# PWRMOD-001-RevA.net
KiCad netlist of a schematic drawn in Altium Designer
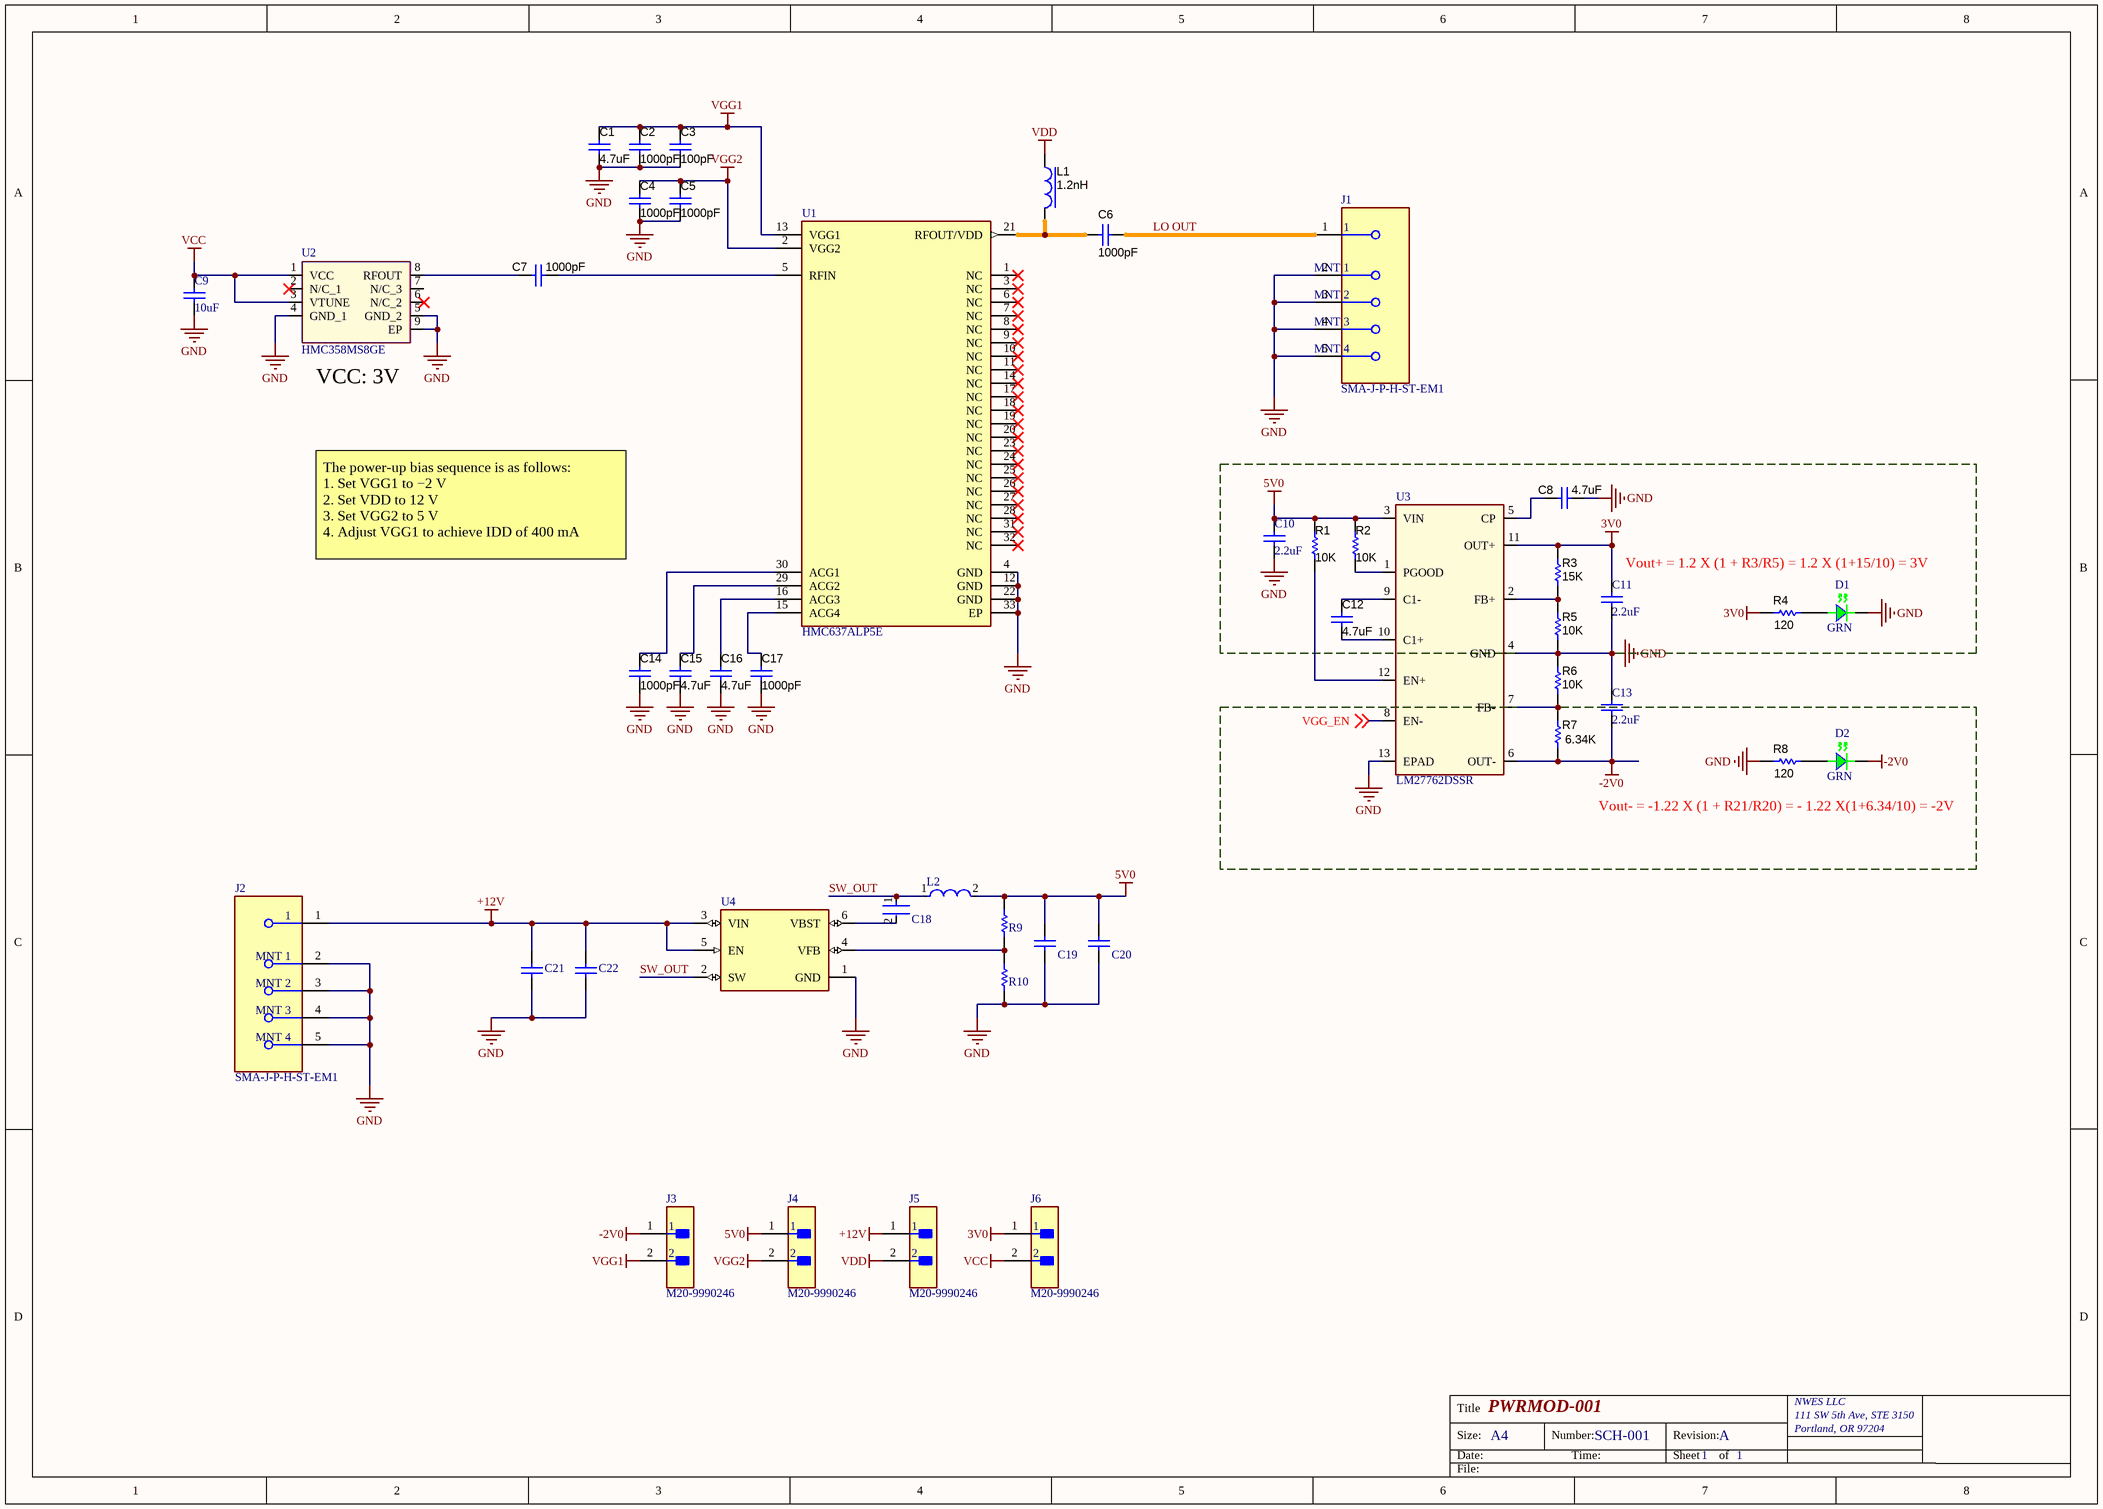
[diagram p0: PWRMOD-001-RevA.SchDoc]

(export (version "E")
  (design (tool "Eeschema 10.0.6"))
  (components
    (comp (ref "C1")
      (value "4.7uF")
      (footprint "0402_CAP")
      (description "CAP CER 4.7UF 10V X5R 0402")
      (fields
        (field (name "MANUFACTURER") "Samsung Electro-Mechanics")
        (field (name "PARTNUMBER") "CL05A475MP5NRNC")
      )
      (libsource (lib "Cold Junction") (part "CAP CER 4.7UF 10V X5R 0402"))
    )
    (comp (ref "C2")
      (value "1000pF")
      (footprint "0402_CAP")
      (description "CAP CER 1000PF 25V X7R 0402")
      (fields
        (field (name "MANUFACTURER") "KEMET")
        (field (name "MANUFACTURER PART NUMBER") "C0402C102J3RECAUTO")
      )
      (libsource (lib "Cold Junction") (part "Capacitor"))
    )
    (comp (ref "C3")
      (value "100pF")
      (footprint "0402_CAP")
      (description "CAP CER 100PF 25V X7R 0402")
      (fields (field (name "MANUFACTURER") "AVX Corporation") (field (name "PARTNUMBER") "04023C101KAT2A"))
      (libsource (lib "Cold Junction") (part "Capacitor"))
    )
    (comp (ref "C4")
      (value "1000pF")
      (footprint "0402_CAP")
      (description "CAP CER 1000PF 25V X7R 0402")
      (fields
        (field (name "MANUFACTURER") "KEMET")
        (field (name "MANUFACTURER PART NUMBER") "C0402C102J3RECAUTO")
      )
      (libsource (lib "Cold Junction") (part "Capacitor"))
    )
    (comp (ref "C5")
      (value "1000pF")
      (footprint "0402_CAP")
      (description "CAP CER 1000PF 25V X7R 0402")
      (fields
        (field (name "MANUFACTURER") "KEMET")
        (field (name "MANUFACTURER PART NUMBER") "C0402C102J3RECAUTO")
      )
      (libsource (lib "Cold Junction") (part "Capacitor"))
    )
    (comp (ref "C6")
      (value "1000pF")
      (footprint "0402_CAP")
      (description "CAP CER 1000PF 25V X7R 0402")
      (fields
        (field (name "MANUFACTURER") "KEMET")
        (field (name "MANUFACTURER PART NUMBER") "C0402C102J3RECAUTO")
      )
      (libsource (lib "Cold Junction") (part "Capacitor"))
    )
    (comp (ref "C7")
      (value "1000pF")
      (footprint "0402_CAP")
      (description "CAP CER 1000PF 50V C0G/NP0 0402")
      (fields
        (field (name "MANUFACTURER") "Murata Electronics")
        (field (name "PARTNUMBER") "GCM1555C1H102FA16D")
      )
      (libsource (lib "Cold Junction") (part "Capacitor"))
    )
    (comp (ref "C8")
      (value "4.7uF")
      (footprint "0402_CAP")
      (description "CAP CER 4.7UF 10V X5R 0402")
      (fields
        (field (name "MANUFACTURER") "Samsung Electro-Mechanics")
        (field (name "PARTNUMBER") "CL05A475MP5NRNC")
      )
      (libsource (lib "Cold Junction") (part "CAP CER 4.7UF 10V X5R 0402"))
    )
    (comp (ref "C9")
      (value "10uF")
      (footprint "0402_CAP")
      (description "CAP CER 10UF 6.3V X5R 0402")
      (fields
        (field (name "MANUFACTURER") "Murata Electronics")
        (field (name "PARTNUMBER") "GRJ155R60J106ME11D")
      )
      (libsource (lib "Cold Junction") (part "Cap"))
    )
    (comp (ref "C10")
      (value "2.2uF")
      (footprint "0402_CAP")
      (description "CAP CER 2.2UF 16V X6S 0402")
      (fields
        (field (name "MANUFACTURER") "TDK Corporation")
        (field (name "PARTNUMBER") "C1005X6S1C225M050BC")
      )
      (libsource (lib "Cold Junction") (part "Cap"))
    )
    (comp (ref "C11")
      (value "2.2uF")
      (footprint "0402_CAP")
      (description "CAP CER 2.2UF 16V X6S 0402")
      (fields
        (field (name "MANUFACTURER") "TDK Corporation")
        (field (name "PARTNUMBER") "C1005X6S1C225M050BC")
      )
      (libsource (lib "Cold Junction") (part "Cap"))
    )
    (comp (ref "C12")
      (value "4.7uF")
      (footprint "0402_CAP")
      (description "CAP CER 4.7UF 10V X5R 0402")
      (fields
        (field (name "MANUFACTURER") "Samsung Electro-Mechanics")
        (field (name "PARTNUMBER") "CL05A475MP5NRNC")
      )
      (libsource (lib "Cold Junction") (part "CAP CER 4.7UF 10V X5R 0402"))
    )
    (comp (ref "C13")
      (value "2.2uF")
      (footprint "0402_CAP")
      (description "CAP CER 2.2UF 16V X6S 0402")
      (fields
        (field (name "MANUFACTURER") "TDK Corporation")
        (field (name "PARTNUMBER") "C1005X6S1C225M050BC")
      )
      (libsource (lib "Cold Junction") (part "Cap"))
    )
    (comp (ref "C14")
      (value "1000pF")
      (footprint "0402_CAP")
      (description "CAP CER 1000PF 25V X7R 0402")
      (fields
        (field (name "MANUFACTURER") "KEMET")
        (field (name "MANUFACTURER PART NUMBER") "C0402C102J3RECAUTO")
      )
      (libsource (lib "Cold Junction") (part "Capacitor"))
    )
    (comp (ref "C15")
      (value "4.7uF")
      (footprint "0402_CAP")
      (description "CAP CER 4.7UF 10V X5R 0402")
      (fields
        (field (name "MANUFACTURER") "Samsung Electro-Mechanics")
        (field (name "PARTNUMBER") "CL05A475MP5NRNC")
      )
      (libsource (lib "Cold Junction") (part "CAP CER 4.7UF 10V X5R 0402"))
    )
    (comp (ref "C16")
      (value "4.7uF")
      (footprint "0402_CAP")
      (description "CAP CER 4.7UF 10V X5R 0402")
      (fields
        (field (name "MANUFACTURER") "Samsung Electro-Mechanics")
        (field (name "PARTNUMBER") "CL05A475MP5NRNC")
      )
      (libsource (lib "Cold Junction") (part "CAP CER 4.7UF 10V X5R 0402"))
    )
    (comp (ref "C17")
      (value "1000pF")
      (footprint "0402_CAP")
      (description "CAP CER 1000PF 25V X7R 0402")
      (fields
        (field (name "MANUFACTURER") "KEMET")
        (field (name "MANUFACTURER PART NUMBER") "C0402C102J3RECAUTO")
      )
      (libsource (lib "Cold Junction") (part "Capacitor"))
    )
    (comp (ref "C18")
      (value "C0603C104Z3VACTU")
      (footprint "FP-C0603-CG-IPC_B")
      (description "CAP CER 0.1UF 25V Y5V 0603")
      (fields (field (name "TOLERANCE") "80%") (field (name "VOLTAGE") "25V"))
      (libsource (lib "Altium Content Vault") (part "02cd4be3c70576c341d710602a673aa"))
    )
    (comp (ref "C19")
      (value "C1608X5R1A226M080AC")
      (footprint "CAPC1608X100X20ML10")
      (description "Chip Capacitor, 22 uF, +/- 20%, 10 V, -55 to 85 degC, 0603 (1608 Metric), RoHS, Tape and Reel")
      (fields (field (name "MANUFACTURER") "TDK") (field (name "TOLERANCE") "±20%"))
      (libsource (lib "Altium Content Vault") (part "CAP-NP-2"))
    )
    (comp (ref "C20")
      (value "C1608X5R1A226M080AC")
      (footprint "CAPC1608X100X20ML10")
      (description "Chip Capacitor, 22 uF, +/- 20%, 10 V, -55 to 85 degC, 0603 (1608 Metric), RoHS, Tape and Reel")
      (fields (field (name "MANUFACTURER") "TDK") (field (name "TOLERANCE") "±20%"))
      (libsource (lib "Altium Content Vault") (part "CAP-NP-2"))
    )
    (comp (ref "C21")
      (value "GRM31CR61E106KA12L")
      (footprint "CAPC3216X180X55ML20T25")
      (description "Chip Capacitor, 10 uF, +/- 10%, 25 V, -55 to 85 degC, 1206 (3216 Metric), RoHS, Tape and Reel")
      (fields (field (name "MANUFACTURER") "Murata") (field (name "TOLERANCE") "10%"))
      (libsource (lib "Altium Content Vault") (part "CAP-NP-2"))
    )
    (comp (ref "C22")
      (value "GRM31CR61E106KA12L")
      (footprint "CAPC3216X180X55ML20T25")
      (description "Chip Capacitor, 10 uF, +/- 10%, 25 V, -55 to 85 degC, 1206 (3216 Metric), RoHS, Tape and Reel")
      (fields (field (name "MANUFACTURER") "Murata") (field (name "TOLERANCE") "10%"))
      (libsource (lib "Altium Content Vault") (part "CAP-NP-2"))
    )
    (comp (ref "D1")
      (value "GRN")
      (footprint "LED_0603")
      (description "LED GREEN CLEAR CHIP 0603 SMD")
      (fields (field (name "MANUFACTURER") "Kingbright") (field (name "PARTNUMBER") "APTD1608CGCK"))
      (libsource (lib "Cold Junction") (part "0603LED_GRN"))
    )
    (comp (ref "D2")
      (value "GRN")
      (footprint "LED_0603")
      (description "LED GREEN CLEAR CHIP 0603 SMD")
      (fields (field (name "MANUFACTURER") "Kingbright") (field (name "PARTNUMBER") "APTD1608CGCK"))
      (libsource (lib "Cold Junction") (part "0603LED_GRN"))
    )
    (comp (ref "J1")
      (value "SMA-J-P-H-ST-EM1")
      (footprint "FP-SMA-J-P-H-ST-EM1-MFG")
      (description "CONN SMA JACK STR 50OHM EDGE MNT")
      (libsource (lib "") (part "c65b8a639cdaef1819ea20b5466f8fa_1"))
    )
    (comp (ref "J2")
      (value "SMA-J-P-H-ST-EM1")
      (footprint "FP-SMA-J-P-H-ST-EM1-MFG")
      (description "CONN SMA JACK STR 50OHM EDGE MNT")
      (libsource (lib "Altium Content Vault") (part "c65b8a639cdaef1819ea20b5466f8fa"))
    )
    (comp (ref "J3")
      (value "M20-9990246")
      (footprint "FP-M20-9990246-MFG")
      (description "CONN HEADER VERT 2POS 2.54MM")
      (fields
        (field (name "OCTOPART") "https://octopart.com/m20-9990246-harwin-2590635")
        (field (name "MANUFACTURER") "Harwin")
      )
      (libsource (lib "Altium Content Vault") (part "3bc925449376181038e59eaffc5286c"))
    )
    (comp (ref "J4")
      (value "M20-9990246")
      (footprint "FP-M20-9990246-MFG")
      (description "CONN HEADER VERT 2POS 2.54MM")
      (fields
        (field (name "OCTOPART") "https://octopart.com/m20-9990246-harwin-2590635")
        (field (name "MANUFACTURER") "Harwin")
      )
      (libsource (lib "Altium Content Vault") (part "3bc925449376181038e59eaffc5286c"))
    )
    (comp (ref "J5")
      (value "M20-9990246")
      (footprint "FP-M20-9990246-MFG")
      (description "CONN HEADER VERT 2POS 2.54MM")
      (fields
        (field (name "OCTOPART") "https://octopart.com/m20-9990246-harwin-2590635")
        (field (name "MANUFACTURER") "Harwin")
      )
      (libsource (lib "Altium Content Vault") (part "3bc925449376181038e59eaffc5286c"))
    )
    (comp (ref "J6")
      (value "M20-9990246")
      (footprint "FP-M20-9990246-MFG")
      (description "CONN HEADER VERT 2POS 2.54MM")
      (fields
        (field (name "OCTOPART") "https://octopart.com/m20-9990246-harwin-2590635")
        (field (name "MANUFACTURER") "Harwin")
      )
      (libsource (lib "Altium Content Vault") (part "3bc925449376181038e59eaffc5286c"))
    )
    (comp (ref "L1")
      (value "1.2nH")
      (footprint "IND_0201")
      (description "FIXED IND 1.2NH 1.1A 40MOHM SMD")
      (fields (field (name "PARTNUMBER") "LQP03HQ1N2B02D") (field (name "MANUFACTURER") "Murata Electronics"))
      (libsource (lib "Cold Junction") (part "INDUCTOR"))
    )
    (comp (ref "L2")
      (value "NRS8030T3R3MJGJ")
      (footprint "FP-NRS8030-MFG")
      (description "Inductor Power Shielded Wirewound 3.3uH 20% 100KHz Ferrite 4.2A 24.7mΩ DCR T/R")
      (fields (field (name "TOLERANCE") "20%"))
      (libsource (lib "Altium Content Vault") (part "725321dda6339637d4d059423bc1c3c"))
    )
    (comp (ref "R1")
      (value "10K")
      (footprint "0402_RES")
      (description "RES 10K OHM 1% 1/16W 0402")
      (fields
        (field (name "PARTNUMBER") "RMCF0402FT10K0")
        (field (name "VALUEDISPLAYED") "10K")
        (field (name "MANUFACTURER") "Stackpole Electronics Inc")
      )
      (libsource (lib "Cold Junction") (part "CMP-0026823-3"))
    )
    (comp (ref "R2")
      (value "10K")
      (footprint "0402_RES")
      (description "RES 10K OHM 1% 1/16W 0402")
      (fields
        (field (name "PARTNUMBER") "RMCF0402FT10K0")
        (field (name "VALUEDISPLAYED") "10K")
        (field (name "MANUFACTURER") "Stackpole Electronics Inc")
      )
      (libsource (lib "Cold Junction") (part "CMP-0026823-3"))
    )
    (comp (ref "R3")
      (value "15K")
      (footprint "0402_RES")
      (description "RES SMD 15K OHM 1% 1/16W 0402")
      (fields
        (field (name "PARTNUMBER") "RC0402FR-0715KL")
        (field (name "VALUEDISPLAYED") "15K")
        (field (name "MANUFACTURER") "Yageo")
      )
      (libsource (lib "Cold Junction") (part "CMP-0026823-3"))
    )
    (comp (ref "R4")
      (value "120")
      (footprint "0402_RES")
      (description "RES 120 OHM 1% 1/16W 0402")
      (fields (field (name "PARTNUMBER") "RC0402FR-07120RL") (field (name "MANUFACTURER") "Yageo"))
      (libsource (lib "Cold Junction") (part "RES 120 OHM 1% 1/16W 0402"))
    )
    (comp (ref "R5")
      (value "10K")
      (footprint "0402_RES")
      (description "RES 10K OHM 1% 1/16W 0402")
      (fields
        (field (name "PARTNUMBER") "RMCF0402FT10K0")
        (field (name "VALUEDISPLAYED") "10K")
        (field (name "MANUFACTURER") "Stackpole Electronics Inc")
      )
      (libsource (lib "Cold Junction") (part "CMP-0026823-3"))
    )
    (comp (ref "R6")
      (value "10K")
      (footprint "0402_RES")
      (description "RES 10K OHM 1% 1/16W 0402")
      (fields
        (field (name "PARTNUMBER") "RMCF0402FT10K0")
        (field (name "VALUEDISPLAYED") "10K")
        (field (name "MANUFACTURER") "Stackpole Electronics Inc")
      )
      (libsource (lib "Cold Junction") (part "CMP-0026823-3"))
    )
    (comp (ref "R7")
      (value "6.34K")
      (footprint "0402_RES")
      (description "RES 6.34K OHM 1% 1/16W 0402")
      (fields (field (name "PARTNUMBER") "RC0402FR-076K34L") (field (name "MANUFACTURER") "Yageo"))
      (libsource (lib "Cold Junction") (part "RES 6.34K OHM 1% 1/16W 0402"))
    )
    (comp (ref "R8")
      (value "120")
      (footprint "0402_RES")
      (description "RES 120 OHM 1% 1/16W 0402")
      (fields (field (name "PARTNUMBER") "RC0402FR-07120RL") (field (name "MANUFACTURER") "Yageo"))
      (libsource (lib "Cold Junction") (part "RES 120 OHM 1% 1/16W 0402"))
    )
    (comp (ref "R9")
      (value "CRCW020156K2FNED")
      (footprint "RESC0603X28X15NL05T05")
      (fields (field (name "MANUFACTURER") "Vishay Dale"))
      (libsource (lib "Altium Content Vault") (part "RES"))
    )
    (comp (ref "R10")
      (value "ERJ2RKF1002X")
      (footprint "RESC1005X40X25LL05T05")
      (description "Chip Resistor, 10 KOhm, +/- 1%, 0.1 W, -55 to 155 degC, 0402 (1005 Metric), RoHS, Tape and Reel")
      (fields (field (name "TOLERANCE") "1%") (field (name "MANUFACTURER") "Panasonic"))
      (libsource (lib "Altium Content Vault") (part "RES-2"))
    )
    (comp (ref "U1")
      (value "HMC637ALP5E")
      (footprint "FP-HCP-32-1-IPC_A")
      (description "IC MMIC MESFET GAAS 1W 32-QFN")
      (libsource (lib "Altium Content Vault") (part "0f5b40441086f0f622d6d4123b0df76"))
    )
    (comp (ref "U2")
      (value "HMC358MS8GE")
      (footprint "SOP65P488X110-9N")
      (description "IC MMIC AMP VCO BUFFER 8-MSOP")
      (fields (field (name "MANUFACTURER") "Analog Devices"))
      (libsource (lib "Cold Junction") (part "HMC358MS8GE"))
    )
    (comp (ref "U3")
      (value "LM27762DSSR")
      (footprint "SON50P200X300X80-13N-D")
      (description "LM27762 LOW-NOISE POSITIVE- AND")
      (fields
        (field (name "MANUFACTURER") "Texas Instruments")
        (field (name "MOUSER PART NUMBER") "595-LM27762DSSR")
      )
      (libsource (lib "Cold Junction") (part "LM27762DSSR"))
    )
    (comp (ref "U4")
      (value "TPS562201DDCR")
      (footprint "FP-DDC0006A-IPC_C")
      (description "IC REG BUCK ADJ 2A TSOT23-6")
      (fields (field (name "MANUFACTURER") "Texas Instruments"))
      (libsource (lib "Altium Content Vault") (part "957e164956730ea4bf6293280af19fc"))
    )
  )
  (nets
    (net (code "1") (name "+12V") (class "Default")
      (node (ref "C21") (pin "2") (pinfunction "2_2") (pintype "passive"))
      (node (ref "C22") (pin "2") (pinfunction "2_2") (pintype "passive"))
      (node (ref "J2") (pin "1") (pinfunction "1_1") (pintype "passive"))
      (node (ref "J5") (pin "1") (pinfunction "1_1") (pintype "passive"))
      (node (ref "U4") (pin "3") (pinfunction "VIN_3") (pintype "bidirectional"))
      (node (ref "U4") (pin "5") (pinfunction "EN_5") (pintype "input"))
    )
    (net (code "2") (name "-2V0") (class "Default")
      (node (ref "C13") (pin "1") (pinfunction "1_1") (pintype "passive"))
      (node (ref "D2") (pin "2") (pinfunction "K_2") (pintype "passive"))
      (node (ref "J3") (pin "1") (pinfunction "1_1") (pintype "passive"))
      (node (ref "R7") (pin "2") (pinfunction "2_2") (pintype "passive"))
      (node (ref "U3") (pin "6") (pinfunction "OUT-_6") (pintype "power_in"))
    )
    (net (code "3") (name "/LO OUT") (class "Default")
      (node (ref "C6") (pin "1") (pinfunction "1_1") (pintype "passive"))
      (node (ref "J1") (pin "1") (pinfunction "1_1") (pintype "passive"))
    )
    (net (code "4") (name "/SW_OUT") (class "Default")
      (node (ref "C18") (pin "1") (pinfunction "1_1") (pintype "passive"))
      (node (ref "L2") (pin "1") (pinfunction "1_1") (pintype "passive"))
      (node (ref "U4") (pin "2") (pinfunction "SW_2") (pintype "bidirectional"))
    )
    (net (code "5") (name "3V0") (class "Default")
      (node (ref "C11") (pin "2") (pinfunction "2_2") (pintype "passive"))
      (node (ref "J6") (pin "1") (pinfunction "1_1") (pintype "passive"))
      (node (ref "R3") (pin "1") (pinfunction "1_1") (pintype "passive"))
      (node (ref "R4") (pin "1") (pinfunction "1_1") (pintype "passive"))
      (node (ref "U3") (pin "11") (pinfunction "OUT+_11") (pintype "power_in"))
    )
    (net (code "6") (name "5V0") (class "Default")
      (node (ref "C10") (pin "2") (pinfunction "2_2") (pintype "passive"))
      (node (ref "C19") (pin "2") (pinfunction "2_2") (pintype "passive"))
      (node (ref "C20") (pin "2") (pinfunction "2_2") (pintype "passive"))
      (node (ref "J4") (pin "1") (pinfunction "1_1") (pintype "passive"))
      (node (ref "L2") (pin "2") (pinfunction "2_2") (pintype "passive"))
      (node (ref "R1") (pin "1") (pinfunction "1_1") (pintype "passive"))
      (node (ref "R2") (pin "1") (pinfunction "1_1") (pintype "passive"))
      (node (ref "R9") (pin "2") (pinfunction "2_2") (pintype "passive"))
      (node (ref "U3") (pin "3") (pinfunction "VIN_3") (pintype "power_in"))
    )
    (net (code "7") (name "GND") (class "Default")
      (node (ref "C1") (pin "1") (pinfunction "1_1") (pintype "passive"))
      (node (ref "C10") (pin "1") (pinfunction "1_1") (pintype "passive"))
      (node (ref "C11") (pin "1") (pinfunction "1_1") (pintype "passive"))
      (node (ref "C13") (pin "2") (pinfunction "2_2") (pintype "passive"))
      (node (ref "C14") (pin "1") (pinfunction "1_1") (pintype "passive"))
      (node (ref "C15") (pin "1") (pinfunction "1_1") (pintype "passive"))
      (node (ref "C16") (pin "1") (pinfunction "1_1") (pintype "passive"))
      (node (ref "C17") (pin "1") (pinfunction "1_1") (pintype "passive"))
      (node (ref "C19") (pin "1") (pinfunction "1_1") (pintype "passive"))
      (node (ref "C2") (pin "1") (pinfunction "1_1") (pintype "passive"))
      (node (ref "C20") (pin "1") (pinfunction "1_1") (pintype "passive"))
      (node (ref "C21") (pin "1") (pinfunction "1_1") (pintype "passive"))
      (node (ref "C22") (pin "1") (pinfunction "1_1") (pintype "passive"))
      (node (ref "C3") (pin "1") (pinfunction "1_1") (pintype "passive"))
      (node (ref "C4") (pin "1") (pinfunction "1_1") (pintype "passive"))
      (node (ref "C5") (pin "1") (pinfunction "1_1") (pintype "passive"))
      (node (ref "C8") (pin "2") (pinfunction "2_2") (pintype "passive"))
      (node (ref "C9") (pin "1") (pinfunction "1_1") (pintype "passive"))
      (node (ref "D1") (pin "2") (pinfunction "K_2") (pintype "passive"))
      (node (ref "J1") (pin "2") (pinfunction "MNT_1_2") (pintype "passive"))
      (node (ref "J1") (pin "3") (pinfunction "MNT_2_3") (pintype "passive"))
      (node (ref "J1") (pin "4") (pinfunction "MNT_3_4") (pintype "passive"))
      (node (ref "J1") (pin "5") (pinfunction "MNT_4_5") (pintype "passive"))
      (node (ref "J2") (pin "2") (pinfunction "MNT_1_2") (pintype "passive"))
      (node (ref "J2") (pin "3") (pinfunction "MNT_2_3") (pintype "passive"))
      (node (ref "J2") (pin "4") (pinfunction "MNT_3_4") (pintype "passive"))
      (node (ref "J2") (pin "5") (pinfunction "MNT_4_5") (pintype "passive"))
      (node (ref "R10") (pin "1") (pinfunction "1_1") (pintype "passive"))
      (node (ref "R5") (pin "2") (pinfunction "2_2") (pintype "passive"))
      (node (ref "R6") (pin "1") (pinfunction "1_1") (pintype "passive"))
      (node (ref "R8") (pin "1") (pinfunction "1_1") (pintype "passive"))
      (node (ref "U1") (pin "12") (pinfunction "GND_12") (pintype "power_in"))
      (node (ref "U1") (pin "22") (pinfunction "GND_22") (pintype "power_in"))
      (node (ref "U1") (pin "33") (pinfunction "EP_33") (pintype "power_in"))
      (node (ref "U1") (pin "4") (pinfunction "GND_4") (pintype "power_in"))
      (node (ref "U2") (pin "4") (pinfunction "GND_1_4") (pintype "passive"))
      (node (ref "U2") (pin "5") (pinfunction "GND_2_5") (pintype "passive"))
      (node (ref "U2") (pin "9") (pinfunction "EP_9") (pintype "passive"))
      (node (ref "U3") (pin "13") (pinfunction "EPAD_13") (pintype "passive"))
      (node (ref "U3") (pin "4") (pinfunction "GND_4") (pintype "passive"))
      (node (ref "U4") (pin "1") (pinfunction "GND_1") (pintype "power_in"))
    )
    (net (code "8") (name "Net-(D1-A)") (class "Default")
      (node (ref "D1") (pin "1") (pinfunction "A_1") (pintype "passive"))
      (node (ref "R4") (pin "2") (pinfunction "2_2") (pintype "passive"))
    )
    (net (code "9") (name "Net-(D2-A)") (class "Default")
      (node (ref "D2") (pin "1") (pinfunction "A_1") (pintype "passive"))
      (node (ref "R8") (pin "2") (pinfunction "2_2") (pintype "passive"))
    )
    (net (code "10") (name "Net-(U1-ACG1)") (class "Default")
      (node (ref "C14") (pin "2") (pinfunction "2_2") (pintype "passive"))
      (node (ref "U1") (pin "30") (pinfunction "ACG1_30") (pintype "power_in"))
    )
    (net (code "11") (name "Net-(U1-ACG2)") (class "Default")
      (node (ref "C15") (pin "2") (pinfunction "2_2") (pintype "passive"))
      (node (ref "U1") (pin "29") (pinfunction "ACG2_29") (pintype "power_in"))
    )
    (net (code "12") (name "Net-(U1-ACG3)") (class "Default")
      (node (ref "C16") (pin "2") (pinfunction "2_2") (pintype "passive"))
      (node (ref "U1") (pin "16") (pinfunction "ACG3_16") (pintype "power_in"))
    )
    (net (code "13") (name "Net-(U1-ACG4)") (class "Default")
      (node (ref "C17") (pin "2") (pinfunction "2_2") (pintype "passive"))
      (node (ref "U1") (pin "15") (pinfunction "ACG4_15") (pintype "power_in"))
    )
    (net (code "14") (name "Net-(U1-RFIN)") (class "Default")
      (node (ref "C7") (pin "2") (pinfunction "2_2") (pintype "passive"))
      (node (ref "U1") (pin "5") (pinfunction "RFIN_5") (pintype "passive"))
    )
    (net (code "15") (name "Net-(U1-RFOUT{slash}VDD)") (class "Default")
      (node (ref "C6") (pin "2") (pinfunction "2_2") (pintype "passive"))
      (node (ref "L1") (pin "2") (pinfunction "2_2") (pintype "passive"))
      (node (ref "U1") (pin "21") (pinfunction "RFOUT/VDD_21") (pintype "output"))
    )
    (net (code "16") (name "Net-(U2-RFOUT)") (class "Default")
      (node (ref "C7") (pin "1") (pinfunction "1_1") (pintype "passive"))
      (node (ref "U2") (pin "8") (pinfunction "RFOUT_8") (pintype "passive"))
    )
    (net (code "17") (name "Net-(U3-C1+)") (class "Default")
      (node (ref "C12") (pin "2") (pinfunction "2_2") (pintype "passive"))
      (node (ref "U3") (pin "10") (pinfunction "C1+_10") (pintype "power_in"))
    )
    (net (code "18") (name "Net-(U3-C1-)") (class "Default")
      (node (ref "C12") (pin "1") (pinfunction "1_1") (pintype "passive"))
      (node (ref "U3") (pin "9") (pinfunction "C1-_9") (pintype "power_in"))
    )
    (net (code "19") (name "Net-(U3-CP)") (class "Default")
      (node (ref "C8") (pin "1") (pinfunction "1_1") (pintype "passive"))
      (node (ref "U3") (pin "5") (pinfunction "CP_5") (pintype "power_in"))
    )
    (net (code "20") (name "Net-(U3-EN+)") (class "Default")
      (node (ref "R1") (pin "2") (pinfunction "2_2") (pintype "passive"))
      (node (ref "U3") (pin "12") (pinfunction "EN+_12") (pintype "passive"))
    )
    (net (code "21") (name "Net-(U3-FB+)") (class "Default")
      (node (ref "R3") (pin "2") (pinfunction "2_2") (pintype "passive"))
      (node (ref "R5") (pin "1") (pinfunction "1_1") (pintype "passive"))
      (node (ref "U3") (pin "2") (pinfunction "FB+_2") (pintype "power_in"))
    )
    (net (code "22") (name "Net-(U3-FB-)") (class "Default")
      (node (ref "R6") (pin "2") (pinfunction "2_2") (pintype "passive"))
      (node (ref "R7") (pin "1") (pinfunction "1_1") (pintype "passive"))
      (node (ref "U3") (pin "7") (pinfunction "FB-_7") (pintype "power_in"))
    )
    (net (code "23") (name "Net-(U3-PGOOD)") (class "Default")
      (node (ref "R2") (pin "2") (pinfunction "2_2") (pintype "passive"))
      (node (ref "U3") (pin "1") (pinfunction "PGOOD_1") (pintype "passive"))
    )
    (net (code "24") (name "Net-(U4-VBST)") (class "Default")
      (node (ref "C18") (pin "2") (pinfunction "2_2") (pintype "passive"))
      (node (ref "U4") (pin "6") (pinfunction "VBST_6") (pintype "bidirectional"))
    )
    (net (code "25") (name "Net-(U4-VFB)") (class "Default")
      (node (ref "R10") (pin "2") (pinfunction "2_2") (pintype "passive"))
      (node (ref "R9") (pin "1") (pinfunction "1_1") (pintype "passive"))
      (node (ref "U4") (pin "4") (pinfunction "VFB_4") (pintype "bidirectional"))
    )
    (net (code "26") (name "VCC") (class "Default")
      (node (ref "C9") (pin "2") (pinfunction "2_2") (pintype "passive"))
      (node (ref "J6") (pin "2") (pinfunction "2_2") (pintype "passive"))
      (node (ref "U2") (pin "1") (pinfunction "VCC_1") (pintype "passive"))
      (node (ref "U2") (pin "3") (pinfunction "VTUNE_3") (pintype "passive"))
    )
    (net (code "27") (name "VDD") (class "Default")
      (node (ref "J5") (pin "2") (pinfunction "2_2") (pintype "passive"))
      (node (ref "L1") (pin "1") (pinfunction "1_1") (pintype "passive"))
    )
    (net (code "28") (name "VGG1") (class "Default")
      (node (ref "C1") (pin "2") (pinfunction "2_2") (pintype "passive"))
      (node (ref "C2") (pin "2") (pinfunction "2_2") (pintype "passive"))
      (node (ref "C3") (pin "2") (pinfunction "2_2") (pintype "passive"))
      (node (ref "J3") (pin "2") (pinfunction "2_2") (pintype "passive"))
      (node (ref "U1") (pin "13") (pinfunction "VGG1_13") (pintype "power_in"))
    )
    (net (code "29") (name "VGG2") (class "Default")
      (node (ref "C4") (pin "2") (pinfunction "2_2") (pintype "passive"))
      (node (ref "C5") (pin "2") (pinfunction "2_2") (pintype "passive"))
      (node (ref "J4") (pin "2") (pinfunction "2_2") (pintype "passive"))
      (node (ref "U1") (pin "2") (pinfunction "VGG2_2") (pintype "power_in"))
    )
    (net (code "30") (name "VGG_EN") (class "Default")
      (node (ref "U3") (pin "8") (pinfunction "EN-_8") (pintype "passive"))
    )
    (net (code "31") (name "unconnected-(U1-NC-Pad1)") (class "Default")
      (node (ref "U1") (pin "1") (pinfunction "NC_1") (pintype "passive+no_connect"))
    )
    (net (code "32") (name "unconnected-(U1-NC-Pad3)") (class "Default")
      (node (ref "U1") (pin "3") (pinfunction "NC_3") (pintype "passive+no_connect"))
    )
    (net (code "33") (name "unconnected-(U1-NC-Pad6)") (class "Default")
      (node (ref "U1") (pin "6") (pinfunction "NC_6") (pintype "passive+no_connect"))
    )
    (net (code "34") (name "unconnected-(U1-NC-Pad7)") (class "Default")
      (node (ref "U1") (pin "7") (pinfunction "NC_7") (pintype "passive+no_connect"))
    )
    (net (code "35") (name "unconnected-(U1-NC-Pad8)") (class "Default")
      (node (ref "U1") (pin "8") (pinfunction "NC_8") (pintype "passive+no_connect"))
    )
    (net (code "36") (name "unconnected-(U1-NC-Pad9)") (class "Default")
      (node (ref "U1") (pin "9") (pinfunction "NC_9") (pintype "passive+no_connect"))
    )
    (net (code "37") (name "unconnected-(U1-NC-Pad10)") (class "Default")
      (node (ref "U1") (pin "10") (pinfunction "NC_10") (pintype "passive+no_connect"))
    )
    (net (code "38") (name "unconnected-(U1-NC-Pad11)") (class "Default")
      (node (ref "U1") (pin "11") (pinfunction "NC_11") (pintype "passive+no_connect"))
    )
    (net (code "39") (name "unconnected-(U1-NC-Pad14)") (class "Default")
      (node (ref "U1") (pin "14") (pinfunction "NC_14") (pintype "passive+no_connect"))
    )
    (net (code "40") (name "unconnected-(U1-NC-Pad17)") (class "Default")
      (node (ref "U1") (pin "17") (pinfunction "NC_17") (pintype "passive+no_connect"))
    )
    (net (code "41") (name "unconnected-(U1-NC-Pad18)") (class "Default")
      (node (ref "U1") (pin "18") (pinfunction "NC_18") (pintype "passive+no_connect"))
    )
    (net (code "42") (name "unconnected-(U1-NC-Pad19)") (class "Default")
      (node (ref "U1") (pin "19") (pinfunction "NC_19") (pintype "passive+no_connect"))
    )
    (net (code "43") (name "unconnected-(U1-NC-Pad20)") (class "Default")
      (node (ref "U1") (pin "20") (pinfunction "NC_20") (pintype "passive+no_connect"))
    )
    (net (code "44") (name "unconnected-(U1-NC-Pad23)") (class "Default")
      (node (ref "U1") (pin "23") (pinfunction "NC_23") (pintype "passive+no_connect"))
    )
    (net (code "45") (name "unconnected-(U1-NC-Pad24)") (class "Default")
      (node (ref "U1") (pin "24") (pinfunction "NC_24") (pintype "passive+no_connect"))
    )
    (net (code "46") (name "unconnected-(U1-NC-Pad25)") (class "Default")
      (node (ref "U1") (pin "25") (pinfunction "NC_25") (pintype "passive+no_connect"))
    )
    (net (code "47") (name "unconnected-(U1-NC-Pad26)") (class "Default")
      (node (ref "U1") (pin "26") (pinfunction "NC_26") (pintype "passive+no_connect"))
    )
    (net (code "48") (name "unconnected-(U1-NC-Pad27)") (class "Default")
      (node (ref "U1") (pin "27") (pinfunction "NC_27") (pintype "passive+no_connect"))
    )
    (net (code "49") (name "unconnected-(U1-NC-Pad28)") (class "Default")
      (node (ref "U1") (pin "28") (pinfunction "NC_28") (pintype "passive+no_connect"))
    )
    (net (code "50") (name "unconnected-(U1-NC-Pad31)") (class "Default")
      (node (ref "U1") (pin "31") (pinfunction "NC_31") (pintype "passive+no_connect"))
    )
    (net (code "51") (name "unconnected-(U1-NC-Pad32)") (class "Default")
      (node (ref "U1") (pin "32") (pinfunction "NC_32") (pintype "passive+no_connect"))
    )
    (net (code "52") (name "unconnected-(U2-N{slash}C_1-Pad2)") (class "Default")
      (node (ref "U2") (pin "2") (pinfunction "N/C_1_2") (pintype "passive+no_connect"))
    )
    (net (code "53") (name "unconnected-(U2-N{slash}C_2-Pad6)") (class "Default")
      (node (ref "U2") (pin "6") (pinfunction "N/C_2_6") (pintype "passive+no_connect"))
    )
    (net (code "54") (name "unconnected-(U2-N{slash}C_3-Pad7)") (class "Default")
      (node (ref "U2") (pin "7") (pinfunction "N/C_3_7") (pintype "passive"))
    )
  )
)
